# feed_sch_2024-06-04.net
KiCad netlist of a schematic drawn in Altium Designer
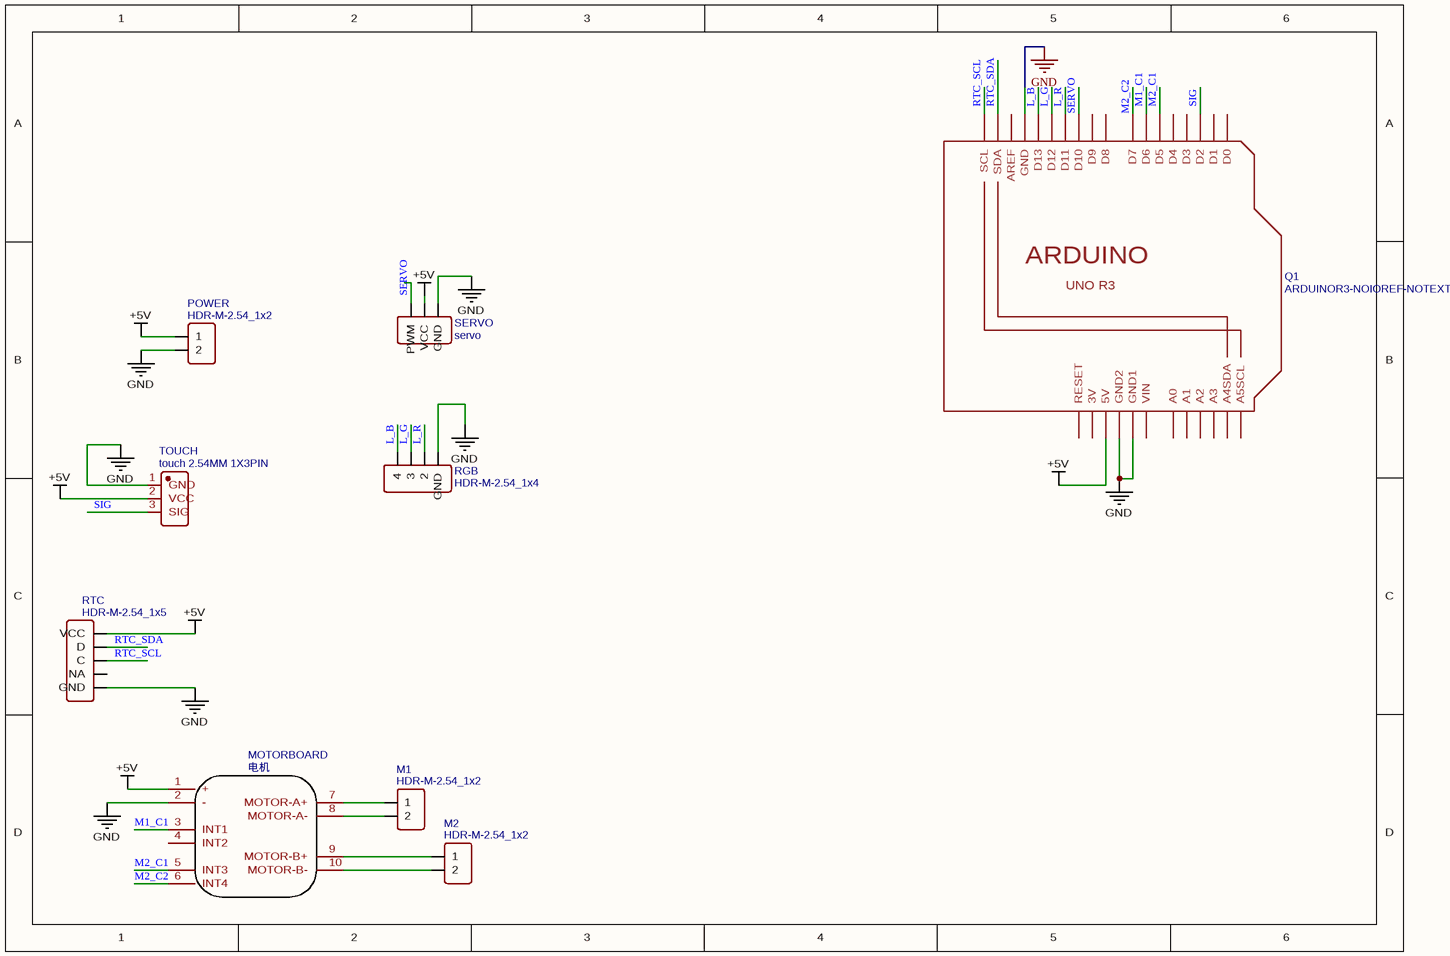
[diagram p0: feed_sch_2024-06-04.schdoc]

(export (version "E")
  (design (tool "Eeschema 10.0.6"))
  (components
    (comp (ref "M1")
      (value "HDR-M-2.54_1x2")
      (footprint "HDR-M-2.54_1X2")
      (fields (field (name "CONTRIBUTOR") "LCEDA_Lib"))
      (libsource (lib "altium-import") (part "root_0_HDR-M-2.54_1x2_"))
    )
    (comp (ref "M2")
      (value "HDR-M-2.54_1x2")
      (footprint "HDR-M-2.54_1X2")
      (fields (field (name "CONTRIBUTOR") "LCEDA_Lib"))
      (libsource (lib "altium-import") (part "root_0_HDR-M-2.54_1x2_"))
    )
    (comp (ref "MOTORBOARD")
      (value "电机")
      (fields (field (name "CONTRIBUTOR") "lzy202040923021"))
      (libsource (lib "altium-import") (part "root_0_电机_"))
    )
    (comp (ref "POWER")
      (value "HDR-M-2.54_1x2")
      (footprint "HDR-M-2.54_1X2")
      (fields (field (name "CONTRIBUTOR") "LCEDA_Lib"))
      (libsource (lib "altium-import") (part "root_0_HDR-M-2.54_1x2_"))
    )
    (comp (ref "Q1")
      (value "ARDUINOR3-NOIOREF-NOTEXT")
      (footprint "ARDUINOR3-NOTEXT-NOIOREF")
      (fields (field (name "CONTRIBUTOR") "Adafruit"))
      (libsource (lib "altium-import") (part "root_0_ARDUINOR3-NOIOREF-NOTEXT_"))
    )
    (comp (ref "RGB")
      (value "HDR-M-2.54_1x4")
      (footprint "HDR-M-2.54_1X4")
      (fields (field (name "CONTRIBUTOR") "aumster"))
      (libsource (lib "altium-import") (part "root_1_HDR-M-2.54_1x4_"))
    )
    (comp (ref "RTC")
      (value "HDR-M-2.54_1x5")
      (footprint "HDR-M-2.54_1X5")
      (fields (field (name "CONTRIBUTOR") "wuyan05"))
      (libsource (lib "altium-import") (part "root_0_HDR-M-2.54_1x5_"))
    )
    (comp (ref "SERVO")
      (value "servo")
      (footprint "HDR-M-2.54_1X3")
      (fields (field (name "CONTRIBUTOR") "tdddddddd"))
      (libsource (lib "altium-import") (part "root_0_servo_"))
    )
    (comp (ref "TOUCH")
      (value "touch 2.54MM 1X3PIN")
      (footprint "HDR-TH_3P-P2.54_CS-1165SDIG")
      (fields (field (name "MANUFACTURER PART") "排母2.54mm 1X3pin") (field (name "CONTRIBUTOR") "lcsc"))
      (libsource (lib "altium-import") (part "root_0_touch 2.54MM 1X3PIN_"))
    )
  )
  (nets
    (net (code "1") (name "+5V") (class "Default")
      (node (ref "MOTORBOARD") (pin "1") (pinfunction "+_1") (pintype "passive"))
      (node (ref "POWER") (pin "1") (pinfunction "1_1") (pintype "passive"))
      (node (ref "Q1") (pin "5V") (pinfunction "5V_5V") (pintype "passive"))
      (node (ref "RTC") (pin "5") (pinfunction "VCC_5") (pintype "passive"))
      (node (ref "SERVO") (pin "2") (pinfunction "VCC_2") (pintype "passive"))
      (node (ref "TOUCH") (pin "2") (pinfunction "VCC_2") (pintype "passive"))
    )
    (net (code "2") (name "/L_B") (class "Default")
      (node (ref "Q1") (pin "D13") (pinfunction "D13_D13") (pintype "passive"))
      (node (ref "RGB") (pin "4") (pinfunction "4_4") (pintype "passive"))
    )
    (net (code "3") (name "/L_G") (class "Default")
      (node (ref "Q1") (pin "D12") (pinfunction "D12_D12") (pintype "passive"))
      (node (ref "RGB") (pin "3") (pinfunction "3_3") (pintype "passive"))
    )
    (net (code "4") (name "/L_R") (class "Default")
      (node (ref "Q1") (pin "D11") (pinfunction "D11_D11") (pintype "passive"))
      (node (ref "RGB") (pin "2") (pinfunction "2_2") (pintype "passive"))
    )
    (net (code "5") (name "/M1_C1") (class "Default")
      (node (ref "MOTORBOARD") (pin "3") (pinfunction "INT1_3") (pintype "passive"))
      (node (ref "Q1") (pin "D6") (pinfunction "D6_D6") (pintype "passive"))
    )
    (net (code "6") (name "/M2_C1") (class "Default")
      (node (ref "MOTORBOARD") (pin "5") (pinfunction "INT3_5") (pintype "passive"))
      (node (ref "Q1") (pin "D5") (pinfunction "D5_D5") (pintype "passive"))
    )
    (net (code "7") (name "/M2_C2") (class "Default")
      (node (ref "MOTORBOARD") (pin "6") (pinfunction "INT4_6") (pintype "passive"))
      (node (ref "Q1") (pin "D7") (pinfunction "D7_D7") (pintype "passive"))
    )
    (net (code "8") (name "/RTC_SCL") (class "Default")
      (node (ref "Q1") (pin "SCL") (pinfunction "SCL_SCL") (pintype "passive"))
      (node (ref "RTC") (pin "3") (pinfunction "C_3") (pintype "passive"))
    )
    (net (code "9") (name "/RTC_SDA") (class "Default")
      (node (ref "Q1") (pin "SDA") (pinfunction "SDA_SDA") (pintype "passive"))
      (node (ref "RTC") (pin "4") (pinfunction "D_4") (pintype "passive"))
    )
    (net (code "10") (name "/SERVO") (class "Default")
      (node (ref "Q1") (pin "D10") (pinfunction "D10_D10") (pintype "passive"))
      (node (ref "SERVO") (pin "3") (pinfunction "PWM_3") (pintype "passive"))
    )
    (net (code "11") (name "/SIG") (class "Default")
      (node (ref "Q1") (pin "D2") (pinfunction "D2_D2") (pintype "passive"))
      (node (ref "TOUCH") (pin "3") (pinfunction "SIG_3") (pintype "passive"))
    )
    (net (code "12") (name "GND") (class "Default")
      (node (ref "MOTORBOARD") (pin "2") (pinfunction "-_2") (pintype "passive"))
      (node (ref "POWER") (pin "2") (pinfunction "2_2") (pintype "passive"))
      (node (ref "Q1") (pin "GND") (pinfunction "GND_GND") (pintype "passive"))
      (node (ref "Q1") (pin "GND1") (pinfunction "GND1_GND1") (pintype "passive"))
      (node (ref "Q1") (pin "GND2") (pinfunction "GND2_GND2") (pintype "passive"))
      (node (ref "RGB") (pin "1") (pinfunction "GND_1") (pintype "passive"))
      (node (ref "RTC") (pin "1") (pinfunction "GND_1") (pintype "passive"))
      (node (ref "SERVO") (pin "1") (pinfunction "GND_1") (pintype "passive"))
      (node (ref "TOUCH") (pin "1") (pinfunction "GND_1") (pintype "passive"))
    )
    (net (code "13") (name "Net-(MOTORBOARD-MOTOR-A+)") (class "Default")
      (node (ref "M1") (pin "1") (pinfunction "1_1") (pintype "passive"))
      (node (ref "MOTORBOARD") (pin "7") (pinfunction "MOTOR-A+_7") (pintype "passive"))
    )
    (net (code "14") (name "Net-(MOTORBOARD-MOTOR-A-)") (class "Default")
      (node (ref "M1") (pin "2") (pinfunction "2_2") (pintype "passive"))
      (node (ref "MOTORBOARD") (pin "8") (pinfunction "MOTOR-A-_8") (pintype "passive"))
    )
    (net (code "15") (name "Net-(MOTORBOARD-MOTOR-B+)") (class "Default")
      (node (ref "M2") (pin "1") (pinfunction "1_1") (pintype "passive"))
      (node (ref "MOTORBOARD") (pin "9") (pinfunction "MOTOR-B+_9") (pintype "passive"))
    )
    (net (code "16") (name "Net-(MOTORBOARD-MOTOR-B-)") (class "Default")
      (node (ref "M2") (pin "2") (pinfunction "2_2") (pintype "passive"))
      (node (ref "MOTORBOARD") (pin "10") (pinfunction "MOTOR-B-_10") (pintype "passive"))
    )
    (net (code "17") (name "unconnected-(MOTORBOARD-INT2-Pad4)") (class "Default")
      (node (ref "MOTORBOARD") (pin "4") (pinfunction "INT2_4") (pintype "passive"))
    )
    (net (code "18") (name "unconnected-(Q1-A4SDA-PadA4)") (class "Default")
      (node (ref "Q1") (pin "A4") (pinfunction "A4SDA_A4") (pintype "passive"))
    )
    (net (code "19") (name "unconnected-(Q1-A5SCL-PadA5)") (class "Default")
      (node (ref "Q1") (pin "A5") (pinfunction "A5SCL_A5") (pintype "passive"))
    )
    (net (code "20") (name "unconnected-(Q1-Pad3V)") (class "Default")
      (node (ref "Q1") (pin "3V") (pinfunction "3V_3V") (pintype "passive"))
    )
    (net (code "21") (name "unconnected-(Q1-PadA0)") (class "Default")
      (node (ref "Q1") (pin "A0") (pinfunction "A0_A0") (pintype "passive"))
    )
    (net (code "22") (name "unconnected-(Q1-PadA1)") (class "Default")
      (node (ref "Q1") (pin "A1") (pinfunction "A1_A1") (pintype "passive"))
    )
    (net (code "23") (name "unconnected-(Q1-PadA2)") (class "Default")
      (node (ref "Q1") (pin "A2") (pinfunction "A2_A2") (pintype "passive"))
    )
    (net (code "24") (name "unconnected-(Q1-PadA3)") (class "Default")
      (node (ref "Q1") (pin "A3") (pinfunction "A3_A3") (pintype "passive"))
    )
    (net (code "25") (name "unconnected-(Q1-PadAREF)") (class "Default")
      (node (ref "Q1") (pin "AREF") (pinfunction "AREF_AREF") (pintype "passive"))
    )
    (net (code "26") (name "unconnected-(Q1-PadD0)") (class "Default")
      (node (ref "Q1") (pin "D0") (pinfunction "D0_D0") (pintype "passive"))
    )
    (net (code "27") (name "unconnected-(Q1-PadD1)") (class "Default")
      (node (ref "Q1") (pin "D1") (pinfunction "D1_D1") (pintype "passive"))
    )
    (net (code "28") (name "unconnected-(Q1-PadD3)") (class "Default")
      (node (ref "Q1") (pin "D3") (pinfunction "D3_D3") (pintype "passive"))
    )
    (net (code "29") (name "unconnected-(Q1-PadD4)") (class "Default")
      (node (ref "Q1") (pin "D4") (pinfunction "D4_D4") (pintype "passive"))
    )
    (net (code "30") (name "unconnected-(Q1-PadD8)") (class "Default")
      (node (ref "Q1") (pin "D8") (pinfunction "D8_D8") (pintype "passive"))
    )
    (net (code "31") (name "unconnected-(Q1-PadD9)") (class "Default")
      (node (ref "Q1") (pin "D9") (pinfunction "D9_D9") (pintype "passive"))
    )
    (net (code "32") (name "unconnected-(Q1-PadRESET)") (class "Default")
      (node (ref "Q1") (pin "RESET") (pinfunction "RESET_RESET") (pintype "passive"))
    )
    (net (code "33") (name "unconnected-(Q1-PadVIN)") (class "Default")
      (node (ref "Q1") (pin "VIN") (pinfunction "VIN_VIN") (pintype "passive"))
    )
    (net (code "34") (name "unconnected-(RTC-NA-Pad2)") (class "Default")
      (node (ref "RTC") (pin "2") (pinfunction "NA_2") (pintype "passive"))
    )
  )
)
